# WL-FRONT.net
KiCad netlist of a schematic drawn in Altium Designer
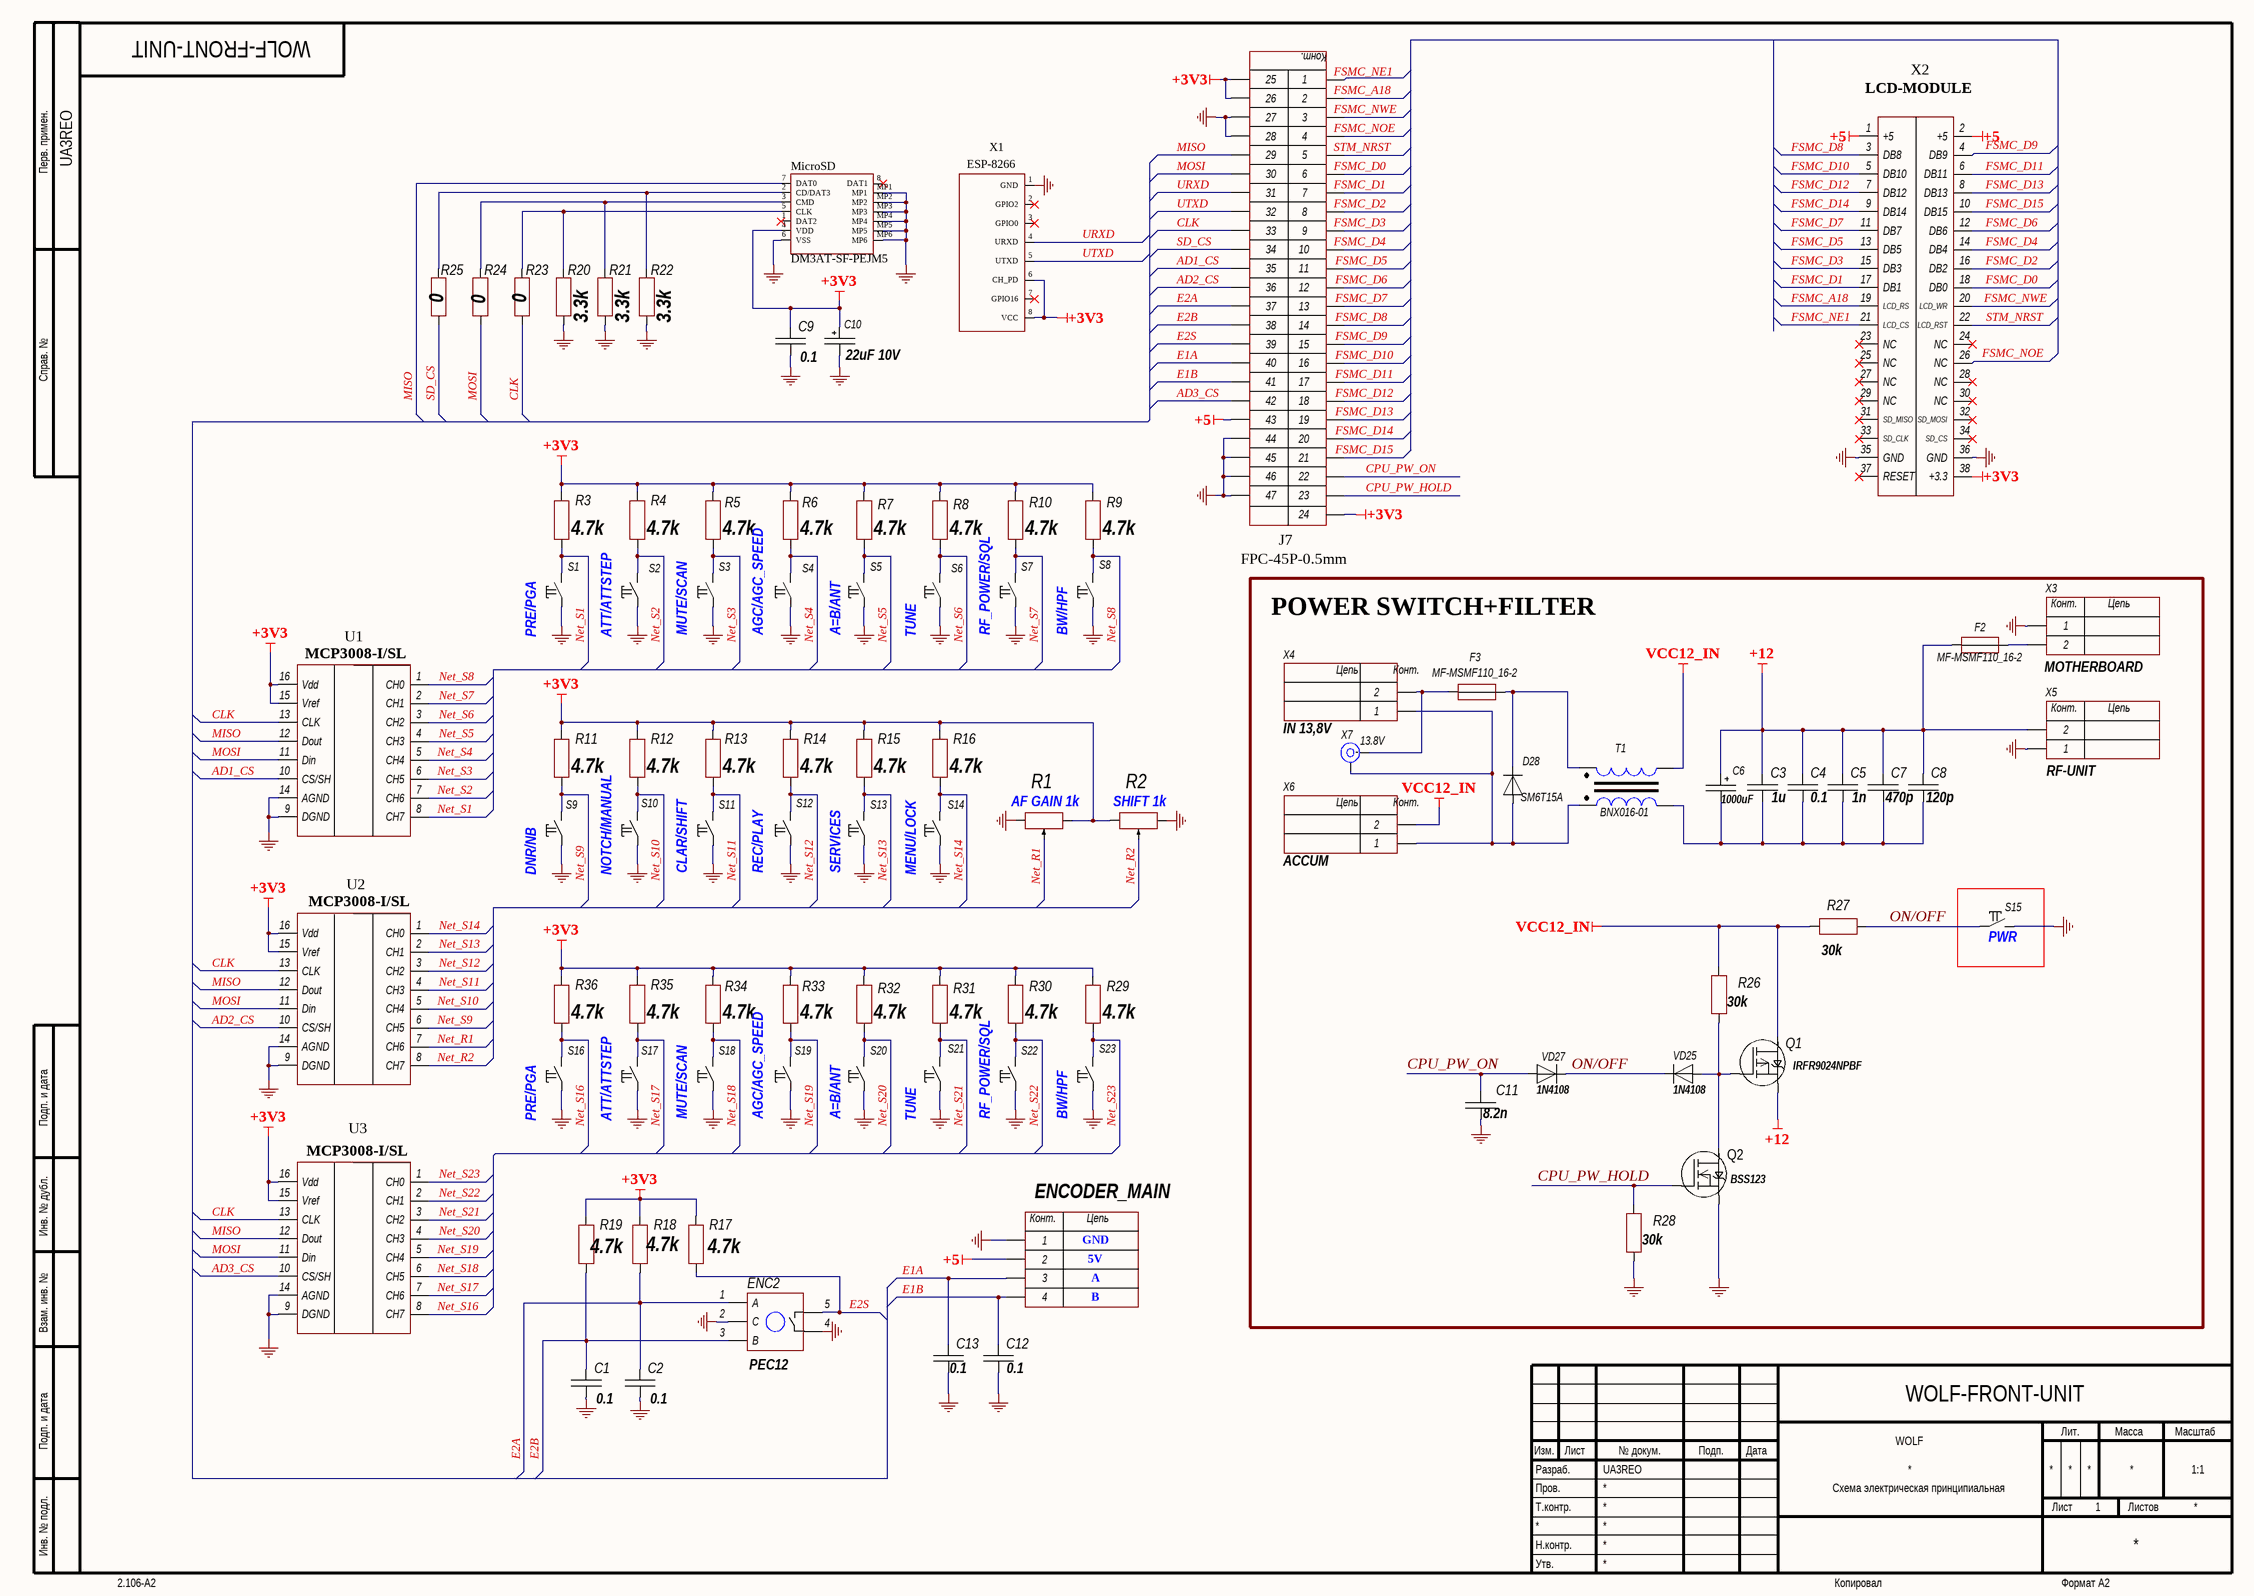
[diagram p0: WL-FRONT.SchDoc]

(export (version "E")
  (design (tool "Eeschema 10.0.6"))
  (components
    (comp (ref "C1")
      (value "0.1")
      (footprint "standard:CH0805C")
      (libsource (lib "Discrete") (part "Capacitor"))
    )
    (comp (ref "C2")
      (value "0.1")
      (footprint "standard:CH0805C")
      (libsource (lib "Discrete") (part "Capacitor"))
    )
    (comp (ref "C3")
      (value "1u")
      (footprint "standard:CH0805C")
      (libsource (lib "Discrete") (part "Capacitor"))
    )
    (comp (ref "C4")
      (value "0.1")
      (footprint "standard:CH0805C")
      (libsource (lib "Discrete") (part "Capacitor"))
    )
    (comp (ref "C5")
      (value "1n")
      (footprint "standard:CH0805C")
      (libsource (lib "Discrete") (part "Capacitor"))
    )
    (comp (ref "C6")
      (value "1000uF")
      (footprint "standard:D5C2H11")
      (libsource (lib "Discrete") (part "AlumCap"))
    )
    (comp (ref "C7")
      (value "470p")
      (footprint "standard:CH0805C")
      (libsource (lib "Discrete") (part "Capacitor"))
    )
    (comp (ref "C8")
      (value "120p")
      (footprint "standard:CH0805C")
      (libsource (lib "Discrete") (part "Capacitor"))
    )
    (comp (ref "C9")
      (value "0.1")
      (footprint "standard:CH0805C")
      (libsource (lib "Discrete") (part "Capacitor"))
    )
    (comp (ref "C10")
      (value "22uF 10V")
      (footprint "standard:TANTAL_B")
      (libsource (lib "Discrete") (part "TantalCap"))
    )
    (comp (ref "C11")
      (value "8.2n")
      (footprint "standard:CH0805C")
      (libsource (lib "Discrete") (part "Capacitor"))
    )
    (comp (ref "C12")
      (value "0.1")
      (footprint "standard:CH0805C")
      (libsource (lib "Discrete") (part "Capacitor"))
    )
    (comp (ref "C13") (value "0.1") (footprint "standard:CH0805C") (libsource (lib "") (part "Capacitor_1")))
    (comp (ref "D28") (value "SM6T15A") (footprint "standard:SOD123") (libsource (lib "Diods") (part "Diod")))
    (comp (ref "ENC2")
      (value "PEC12")
      (footprint "custom:ENC: PEC-12")
      (description "Encoder")
      (libsource (lib "Connectors") (part "PEC12"))
    )
    (comp (ref "ENCODER_MAIN")
      (value "*")
      (footprint "custom:CON: 0010321041")
      (libsource (lib "Connectors") (part "4-Connector"))
    )
    (comp (ref "F2")
      (value "MF-MSMF110_16-2")
      (footprint "standard:CH0603F")
      (libsource (lib "") (part "Fuse_1"))
    )
    (comp (ref "F3")
      (value "MF-MSMF110_16-2")
      (footprint "standard:CH0603F")
      (libsource (lib "Discrete") (part "Fuse"))
    )
    (comp (ref "J7")
      (value "FPC-45P-0.5mm")
      (footprint "FPC-45-0.5")
      (libsource (lib "Connectors") (part "47-PIN"))
    )
    (comp (ref "MicroSD") (value "DM3AT-SF-PEJM5") (libsource (lib "Discrete") (part "MicroSD")))
    (comp (ref "Q1")
      (value "IRFR9024NPBF")
      (footprint "D2PAK_132")
      (libsource (lib "Transistor") (part "P-KANAL"))
    )
    (comp (ref "Q2") (value "BSS123") (footprint "SOT23_132") (libsource (lib "Transistor") (part "N-KANAL")))
    (comp (ref "R1")
      (value "AF GAIN 1k")
      (footprint "custom:RES: 3296W")
      (libsource (lib "Discrete") (part "ADJ resistor"))
    )
    (comp (ref "R2")
      (value "SHIFT 1k")
      (footprint "custom:RES: 3296W")
      (libsource (lib "Discrete") (part "ADJ resistor"))
    )
    (comp (ref "R3")
      (value "4.7k")
      (footprint "standard:CH0805R")
      (libsource (lib "Discrete") (part "Resistor"))
    )
    (comp (ref "R4")
      (value "4.7k")
      (footprint "standard:CH0805R")
      (libsource (lib "Discrete") (part "Resistor"))
    )
    (comp (ref "R5")
      (value "4.7k")
      (footprint "standard:CH0805R")
      (libsource (lib "Discrete") (part "Resistor"))
    )
    (comp (ref "R6")
      (value "4.7k")
      (footprint "standard:CH0805R")
      (libsource (lib "Discrete") (part "Resistor"))
    )
    (comp (ref "R7")
      (value "4.7k")
      (footprint "standard:CH0805R")
      (libsource (lib "Discrete") (part "Resistor"))
    )
    (comp (ref "R8")
      (value "4.7k")
      (footprint "standard:CH0805R")
      (libsource (lib "Discrete") (part "Resistor"))
    )
    (comp (ref "R9")
      (value "4.7k")
      (footprint "standard:CH0805R")
      (libsource (lib "Discrete") (part "Resistor"))
    )
    (comp (ref "R10")
      (value "4.7k")
      (footprint "standard:CH0805R")
      (libsource (lib "Discrete") (part "Resistor"))
    )
    (comp (ref "R11")
      (value "4.7k")
      (footprint "standard:CH0805R")
      (libsource (lib "Discrete") (part "Resistor"))
    )
    (comp (ref "R12")
      (value "4.7k")
      (footprint "standard:CH0805R")
      (libsource (lib "Discrete") (part "Resistor"))
    )
    (comp (ref "R13")
      (value "4.7k")
      (footprint "standard:CH0805R")
      (libsource (lib "Discrete") (part "Resistor"))
    )
    (comp (ref "R14")
      (value "4.7k")
      (footprint "standard:CH0805R")
      (libsource (lib "Discrete") (part "Resistor"))
    )
    (comp (ref "R15")
      (value "4.7k")
      (footprint "standard:CH0805R")
      (libsource (lib "Discrete") (part "Resistor"))
    )
    (comp (ref "R16")
      (value "4.7k")
      (footprint "standard:CH0805R")
      (libsource (lib "Discrete") (part "Resistor"))
    )
    (comp (ref "R17")
      (value "4.7k")
      (footprint "standard:CH0805R")
      (libsource (lib "Discrete") (part "Resistor"))
    )
    (comp (ref "R18")
      (value "4.7k")
      (footprint "standard:CH0805R")
      (libsource (lib "Discrete") (part "Resistor"))
    )
    (comp (ref "R19")
      (value "4.7k")
      (footprint "standard:CH0805R")
      (libsource (lib "Discrete") (part "Resistor"))
    )
    (comp (ref "R20")
      (value "3.3k")
      (footprint "standard:CH0805R")
      (libsource (lib "Discrete") (part "Resistor"))
    )
    (comp (ref "R21")
      (value "3.3k")
      (footprint "standard:CH0805R")
      (libsource (lib "Discrete") (part "Resistor"))
    )
    (comp (ref "R22")
      (value "3.3k")
      (footprint "standard:CH0805R")
      (libsource (lib "Discrete") (part "Resistor"))
    )
    (comp (ref "R23") (value "0") (footprint "standard:CH0805R") (libsource (lib "") (part "Resistor_1")))
    (comp (ref "R24") (value "0") (footprint "standard:CH0805R") (libsource (lib "") (part "Resistor_1")))
    (comp (ref "R25") (value "0") (footprint "standard:CH0805R") (libsource (lib "") (part "Resistor_1")))
    (comp (ref "R26")
      (value "30k")
      (footprint "standard:CH0805R")
      (libsource (lib "Discrete") (part "Resistor"))
    )
    (comp (ref "R27") (value "30k") (footprint "standard:CH0805R") (libsource (lib "") (part "Resistor_2")))
    (comp (ref "R28")
      (value "30k")
      (footprint "standard:CH0805R")
      (libsource (lib "Discrete") (part "Resistor"))
    )
    (comp (ref "R29")
      (value "4.7k")
      (footprint "standard:CH0805R")
      (libsource (lib "Discrete") (part "Resistor"))
    )
    (comp (ref "R30")
      (value "4.7k")
      (footprint "standard:CH0805R")
      (libsource (lib "Discrete") (part "Resistor"))
    )
    (comp (ref "R31")
      (value "4.7k")
      (footprint "standard:CH0805R")
      (libsource (lib "Discrete") (part "Resistor"))
    )
    (comp (ref "R32")
      (value "4.7k")
      (footprint "standard:CH0805R")
      (libsource (lib "Discrete") (part "Resistor"))
    )
    (comp (ref "R33")
      (value "4.7k")
      (footprint "standard:CH0805R")
      (libsource (lib "Discrete") (part "Resistor"))
    )
    (comp (ref "R34")
      (value "4.7k")
      (footprint "standard:CH0805R")
      (libsource (lib "Discrete") (part "Resistor"))
    )
    (comp (ref "R35")
      (value "4.7k")
      (footprint "standard:CH0805R")
      (libsource (lib "Discrete") (part "Resistor"))
    )
    (comp (ref "R36")
      (value "4.7k")
      (footprint "standard:CH0805R")
      (libsource (lib "Discrete") (part "Resistor"))
    )
    (comp (ref "S1")
      (value "PRE/PGA")
      (footprint "Botoom-1")
      (description "6x6 mm")
      (libsource (lib "Connectors") (part "Tactile switches"))
    )
    (comp (ref "S2")
      (value "ATT/ATTSTEP")
      (footprint "Botoom-1")
      (description "6x6 mm")
      (libsource (lib "Connectors") (part "Tactile switches"))
    )
    (comp (ref "S3")
      (value "MUTE/SCAN")
      (footprint "Botoom-1")
      (description "6x6 mm")
      (libsource (lib "Connectors") (part "Tactile switches"))
    )
    (comp (ref "S4")
      (value "AGC/AGC_SPEED")
      (footprint "Botoom-1")
      (description "6x6 mm")
      (libsource (lib "Connectors") (part "Tactile switches"))
    )
    (comp (ref "S5")
      (value "A=B/ANT")
      (footprint "Botoom-1")
      (description "6x6 mm")
      (libsource (lib "Connectors") (part "Tactile switches"))
    )
    (comp (ref "S6")
      (value "TUNE")
      (footprint "Botoom-1")
      (description "6x6 mm")
      (libsource (lib "Connectors") (part "Tactile switches"))
    )
    (comp (ref "S7")
      (value "RF_POWER/SQL")
      (footprint "Botoom-1")
      (description "6x6 mm")
      (libsource (lib "Connectors") (part "Tactile switches"))
    )
    (comp (ref "S8")
      (value "BW/HPF")
      (footprint "Botoom-1")
      (description "6x6 mm")
      (libsource (lib "Connectors") (part "Tactile switches"))
    )
    (comp (ref "S9")
      (value "DNR/NB")
      (footprint "Botoom-1")
      (description "6x6 mm")
      (libsource (lib "Connectors") (part "Tactile switches"))
    )
    (comp (ref "S10")
      (value "NOTCH/MANUAL")
      (footprint "Botoom-1")
      (description "6x6 mm")
      (libsource (lib "Connectors") (part "Tactile switches"))
    )
    (comp (ref "S11")
      (value "CLAR/SHIFT")
      (footprint "Botoom-1")
      (description "6x6 mm")
      (libsource (lib "Connectors") (part "Tactile switches"))
    )
    (comp (ref "S12")
      (value "REC/PLAY")
      (footprint "Botoom-1")
      (description "6x6 mm")
      (libsource (lib "Connectors") (part "Tactile switches"))
    )
    (comp (ref "S13")
      (value "SERVICES")
      (footprint "Botoom-1")
      (description "6x6 mm")
      (libsource (lib "Connectors") (part "Tactile switches"))
    )
    (comp (ref "S14")
      (value "MENU/LOCK")
      (footprint "Botoom-1")
      (description "6x6 mm")
      (libsource (lib "Connectors") (part "Tactile switches"))
    )
    (comp (ref "S15")
      (value "PWR")
      (footprint "Botoom-1")
      (description "6x6 mm")
      (libsource (lib "Connectors") (part "Tactile switches"))
    )
    (comp (ref "S16")
      (value "PRE/PGA")
      (footprint "Botoom-1")
      (description "6x6 mm")
      (libsource (lib "Connectors") (part "Tactile switches"))
    )
    (comp (ref "S17")
      (value "ATT/ATTSTEP")
      (footprint "Botoom-1")
      (description "6x6 mm")
      (libsource (lib "Connectors") (part "Tactile switches"))
    )
    (comp (ref "S18")
      (value "MUTE/SCAN")
      (footprint "Botoom-1")
      (description "6x6 mm")
      (libsource (lib "Connectors") (part "Tactile switches"))
    )
    (comp (ref "S19")
      (value "AGC/AGC_SPEED")
      (footprint "Botoom-1")
      (description "6x6 mm")
      (libsource (lib "Connectors") (part "Tactile switches"))
    )
    (comp (ref "S20")
      (value "A=B/ANT")
      (footprint "Botoom-1")
      (description "6x6 mm")
      (libsource (lib "Connectors") (part "Tactile switches"))
    )
    (comp (ref "S21")
      (value "TUNE")
      (footprint "Botoom-1")
      (description "6x6 mm")
      (libsource (lib "Connectors") (part "Tactile switches"))
    )
    (comp (ref "S22")
      (value "RF_POWER/SQL")
      (footprint "Botoom-1")
      (description "6x6 mm")
      (libsource (lib "Connectors") (part "Tactile switches"))
    )
    (comp (ref "S23")
      (value "BW/HPF")
      (footprint "Botoom-1")
      (description "6x6 mm")
      (libsource (lib "Connectors") (part "Tactile switches"))
    )
    (comp (ref "T1")
      (value "BNX016-01")
      (footprint "custom:TRANS: DLW21")
      (fields (field (name "MANUFACTURER") "Murata Electronics North America"))
      (libsource (lib "Transformers") (part "EMI bead"))
    )
    (comp (ref "U1")
      (value "MCP3008-I/SL")
      (footprint "16-SOIC")
      (libsource (lib "Digital") (part "MCP3008-I/SL"))
    )
    (comp (ref "U2")
      (value "MCP3008-I/SL")
      (footprint "16-SOIC")
      (libsource (lib "Digital") (part "MCP3008-I/SL"))
    )
    (comp (ref "U3")
      (value "MCP3008-I/SL")
      (footprint "16-SOIC")
      (libsource (lib "Digital") (part "MCP3008-I/SL"))
    )
    (comp (ref "VD25") (value "1N4108") (footprint "1N4148") (libsource (lib "Diods") (part "Diod")))
    (comp (ref "VD27") (value "1N4108") (footprint "1N4148") (libsource (lib "Diods") (part "Diod")))
    (comp (ref "X1") (value "ESP-8266") (libsource (lib "Discrete") (part "ESP-8266")))
    (comp (ref "X2")
      (value "LCD-MODULE")
      (footprint "TFT3.2-320x480-pin")
      (libsource (lib "Digital") (part "LCD-MODULE"))
    )
    (comp (ref "X3")
      (value "MOTHERBOARD")
      (footprint "custom:CON: 300-02P-5.0")
      (libsource (lib "") (part "2-Connector_1"))
    )
    (comp (ref "X4")
      (value "IN 13,8V")
      (footprint "custom:CON: 300-02P-5.0")
      (libsource (lib "") (part "2-Connector_2"))
    )
    (comp (ref "X5")
      (value "RF-UNIT")
      (footprint "custom:CON: 300-02P-5.0")
      (libsource (lib "Connectors") (part "2-Connector"))
    )
    (comp (ref "X6")
      (value "ACCUM")
      (footprint "custom:CON: 300-02P-5.0")
      (libsource (lib "") (part "2-Connector_2"))
    )
    (comp (ref "X7")
      (value "13.8V")
      (footprint "custom:CON: PJ-102AH")
      (description "RF")
      (fields (field (name "MANUFACTURER") "CUI Inc."))
      (libsource (lib "Connectors") (part "Power"))
    )
  )
  (nets
    (net (code "1") (name "+3V3") (class "Default")
      (node (ref "C10") (pin "1") (pinfunction "1_1") (pintype "power_in"))
      (node (ref "C9") (pin "2") (pinfunction "2_2") (pintype "power_in"))
      (node (ref "J7") (pin "24") (pinfunction "24_24") (pintype "power_in"))
      (node (ref "J7") (pin "25") (pinfunction "25_25") (pintype "power_in"))
      (node (ref "J7") (pin "26") (pinfunction "26_26") (pintype "power_in"))
      (node (ref "MicroSD") (pin "4") (pinfunction "VDD_4") (pintype "passive"))
      (node (ref "R1") (pin "3") (pinfunction "3_3") (pintype "passive"))
      (node (ref "R10") (pin "2") (pinfunction "2_2") (pintype "passive"))
      (node (ref "R11") (pin "2") (pinfunction "2_2") (pintype "passive"))
      (node (ref "R12") (pin "2") (pinfunction "2_2") (pintype "passive"))
      (node (ref "R13") (pin "2") (pinfunction "2_2") (pintype "passive"))
      (node (ref "R14") (pin "2") (pinfunction "2_2") (pintype "passive"))
      (node (ref "R15") (pin "2") (pinfunction "2_2") (pintype "passive"))
      (node (ref "R16") (pin "2") (pinfunction "2_2") (pintype "passive"))
      (node (ref "R17") (pin "2") (pinfunction "2_2") (pintype "passive"))
      (node (ref "R18") (pin "2") (pinfunction "2_2") (pintype "passive"))
      (node (ref "R19") (pin "2") (pinfunction "2_2") (pintype "passive"))
      (node (ref "R2") (pin "1") (pinfunction "1_1") (pintype "passive"))
      (node (ref "R29") (pin "2") (pinfunction "2_2") (pintype "passive"))
      (node (ref "R3") (pin "2") (pinfunction "2_2") (pintype "passive"))
      (node (ref "R30") (pin "2") (pinfunction "2_2") (pintype "passive"))
      (node (ref "R31") (pin "2") (pinfunction "2_2") (pintype "passive"))
      (node (ref "R32") (pin "2") (pinfunction "2_2") (pintype "passive"))
      (node (ref "R33") (pin "2") (pinfunction "2_2") (pintype "passive"))
      (node (ref "R34") (pin "2") (pinfunction "2_2") (pintype "passive"))
      (node (ref "R35") (pin "2") (pinfunction "2_2") (pintype "passive"))
      (node (ref "R36") (pin "2") (pinfunction "2_2") (pintype "passive"))
      (node (ref "R4") (pin "2") (pinfunction "2_2") (pintype "passive"))
      (node (ref "R5") (pin "2") (pinfunction "2_2") (pintype "passive"))
      (node (ref "R6") (pin "2") (pinfunction "2_2") (pintype "passive"))
      (node (ref "R7") (pin "2") (pinfunction "2_2") (pintype "passive"))
      (node (ref "R8") (pin "2") (pinfunction "2_2") (pintype "passive"))
      (node (ref "R9") (pin "2") (pinfunction "2_2") (pintype "passive"))
      (node (ref "U1") (pin "15") (pinfunction "Vref_15") (pintype "passive"))
      (node (ref "U1") (pin "16") (pinfunction "Vdd_16") (pintype "passive"))
      (node (ref "U2") (pin "15") (pinfunction "Vref_15") (pintype "passive"))
      (node (ref "U2") (pin "16") (pinfunction "Vdd_16") (pintype "passive"))
      (node (ref "U3") (pin "15") (pinfunction "Vref_15") (pintype "passive"))
      (node (ref "U3") (pin "16") (pinfunction "Vdd_16") (pintype "passive"))
      (node (ref "X1") (pin "6") (pinfunction "CH_PD_6") (pintype "passive"))
      (node (ref "X1") (pin "8") (pinfunction "VCC_8") (pintype "passive"))
      (node (ref "X2") (pin "38") (pinfunction "+3.3_38") (pintype "passive"))
    )
    (net (code "2") (name "+5") (class "Default")
      (node (ref "ENCODER_MAIN") (pin "2") (pinfunction "2_2") (pintype "passive"))
      (node (ref "J7") (pin "43") (pinfunction "43_43") (pintype "power_in"))
      (node (ref "X2") (pin "1") (pinfunction "+5_1") (pintype "passive"))
      (node (ref "X2") (pin "2") (pinfunction "+5_2") (pintype "passive"))
    )
    (net (code "3") (name "+12") (class "Default")
      (node (ref "C3") (pin "2") (pinfunction "2_2") (pintype "power_in"))
      (node (ref "C4") (pin "2") (pinfunction "2_2") (pintype "power_in"))
      (node (ref "C5") (pin "2") (pinfunction "2_2") (pintype "power_in"))
      (node (ref "C6") (pin "1") (pinfunction "1_1") (pintype "power_in"))
      (node (ref "C7") (pin "2") (pinfunction "2_2") (pintype "power_in"))
      (node (ref "C8") (pin "2") (pinfunction "2_2") (pintype "power_in"))
      (node (ref "F2") (pin "1") (pinfunction "1_1") (pintype "passive"))
      (node (ref "Q1") (pin "2") (pinfunction "I_2") (pintype "passive"))
      (node (ref "X5") (pin "2") (pinfunction "2_2") (pintype "passive"))
    )
    (net (code "4") (name "/AD1_CS") (class "Default")
      (node (ref "J7") (pin "35") (pinfunction "35_35") (pintype "power_in"))
      (node (ref "U1") (pin "10") (pinfunction "CS/SH_10") (pintype "passive"))
    )
    (net (code "5") (name "/AD2_CS") (class "Default")
      (node (ref "J7") (pin "36") (pinfunction "36_36") (pintype "power_in"))
      (node (ref "U2") (pin "10") (pinfunction "CS/SH_10") (pintype "passive"))
    )
    (net (code "6") (name "/AD3_CS") (class "Default")
      (node (ref "J7") (pin "42") (pinfunction "42_42") (pintype "power_in"))
      (node (ref "U3") (pin "10") (pinfunction "CS/SH_10") (pintype "passive"))
    )
    (net (code "7") (name "/CLK") (class "Default")
      (node (ref "J7") (pin "33") (pinfunction "33_33") (pintype "power_in"))
      (node (ref "R23") (pin "2") (pinfunction "2_2") (pintype "passive"))
      (node (ref "U1") (pin "13") (pinfunction "CLK_13") (pintype "passive"))
      (node (ref "U2") (pin "13") (pinfunction "CLK_13") (pintype "passive"))
      (node (ref "U3") (pin "13") (pinfunction "CLK_13") (pintype "passive"))
    )
    (net (code "8") (name "/CPU_PW_HOLD") (class "Default")
      (node (ref "J7") (pin "23") (pinfunction "23_23") (pintype "power_in"))
      (node (ref "Q2") (pin "1") (pinfunction "Затвор(Gate)_1") (pintype "passive"))
      (node (ref "R28") (pin "2") (pinfunction "2_2") (pintype "passive"))
    )
    (net (code "9") (name "/CPU_PW_ON") (class "Default")
      (node (ref "C11") (pin "1") (pinfunction "1_1") (pintype "power_in"))
      (node (ref "J7") (pin "22") (pinfunction "22_22") (pintype "power_in"))
      (node (ref "VD27") (pin "1") (pinfunction "1_1") (pintype "passive"))
    )
    (net (code "10") (name "/E1A") (class "Default")
      (node (ref "C13") (pin "2") (pinfunction "2_2") (pintype "power_in"))
      (node (ref "ENCODER_MAIN") (pin "3") (pinfunction "3_3") (pintype "power_in"))
      (node (ref "J7") (pin "40") (pinfunction "40_40") (pintype "power_in"))
    )
    (net (code "11") (name "/E1B") (class "Default")
      (node (ref "C12") (pin "2") (pinfunction "2_2") (pintype "power_in"))
      (node (ref "ENCODER_MAIN") (pin "4") (pinfunction "4_4") (pintype "power_in"))
      (node (ref "J7") (pin "41") (pinfunction "41_41") (pintype "power_in"))
    )
    (net (code "12") (name "/E2A") (class "Default")
      (node (ref "C2") (pin "2") (pinfunction "2_2") (pintype "power_in"))
      (node (ref "ENC2") (pin "1") (pinfunction "A_1") (pintype "passive"))
      (node (ref "J7") (pin "37") (pinfunction "37_37") (pintype "power_in"))
      (node (ref "R18") (pin "1") (pinfunction "1_1") (pintype "passive"))
    )
    (net (code "13") (name "/E2B") (class "Default")
      (node (ref "C1") (pin "2") (pinfunction "2_2") (pintype "power_in"))
      (node (ref "ENC2") (pin "3") (pinfunction "B_3") (pintype "passive"))
      (node (ref "J7") (pin "38") (pinfunction "38_38") (pintype "power_in"))
      (node (ref "R19") (pin "1") (pinfunction "1_1") (pintype "passive"))
    )
    (net (code "14") (name "/E2S") (class "Default")
      (node (ref "ENC2") (pin "5") (pinfunction "5_5") (pintype "passive"))
      (node (ref "J7") (pin "39") (pinfunction "39_39") (pintype "power_in"))
      (node (ref "R17") (pin "1") (pinfunction "1_1") (pintype "passive"))
    )
    (net (code "15") (name "/FSMC_A18") (class "Default")
      (node (ref "X2") (pin "19") (pinfunction "LCD_RS_19") (pintype "passive"))
    )
    (net (code "16") (name "/FSMC_D0") (class "Default")
      (node (ref "X2") (pin "18") (pinfunction "DB0_18") (pintype "passive"))
    )
    (net (code "17") (name "/FSMC_D1") (class "Default")
      (node (ref "X2") (pin "17") (pinfunction "DB1_17") (pintype "passive"))
    )
    (net (code "18") (name "/FSMC_D2") (class "Default")
      (node (ref "X2") (pin "16") (pinfunction "DB2_16") (pintype "passive"))
    )
    (net (code "19") (name "/FSMC_D3") (class "Default")
      (node (ref "X2") (pin "15") (pinfunction "DB3_15") (pintype "passive"))
    )
    (net (code "20") (name "/FSMC_D4") (class "Default")
      (node (ref "X2") (pin "14") (pinfunction "DB4_14") (pintype "passive"))
    )
    (net (code "21") (name "/FSMC_D5") (class "Default")
      (node (ref "X2") (pin "13") (pinfunction "DB5_13") (pintype "passive"))
    )
    (net (code "22") (name "/FSMC_D6") (class "Default")
      (node (ref "X2") (pin "12") (pinfunction "DB6_12") (pintype "passive"))
    )
    (net (code "23") (name "/FSMC_D7") (class "Default")
      (node (ref "X2") (pin "11") (pinfunction "DB7_11") (pintype "passive"))
    )
    (net (code "24") (name "/FSMC_D8") (class "Default")
      (node (ref "X2") (pin "3") (pinfunction "DB8_3") (pintype "passive"))
    )
    (net (code "25") (name "/FSMC_D9") (class "Default")
      (node (ref "X2") (pin "4") (pinfunction "DB9_4") (pintype "passive"))
    )
    (net (code "26") (name "/FSMC_D10") (class "Default")
      (node (ref "X2") (pin "5") (pinfunction "DB10_5") (pintype "passive"))
    )
    (net (code "27") (name "/FSMC_D11") (class "Default")
      (node (ref "X2") (pin "6") (pinfunction "DB11_6") (pintype "passive"))
    )
    (net (code "28") (name "/FSMC_D12") (class "Default")
      (node (ref "X2") (pin "7") (pinfunction "DB12_7") (pintype "passive"))
    )
    (net (code "29") (name "/FSMC_D13") (class "Default")
      (node (ref "X2") (pin "8") (pinfunction "DB13_8") (pintype "passive"))
    )
    (net (code "30") (name "/FSMC_D14") (class "Default")
      (node (ref "X2") (pin "9") (pinfunction "DB14_9") (pintype "passive"))
    )
    (net (code "31") (name "/FSMC_D15") (class "Default")
      (node (ref "X2") (pin "10") (pinfunction "DB15_10") (pintype "passive"))
    )
    (net (code "32") (name "/FSMC_NE1") (class "Default")
      (node (ref "X2") (pin "21") (pinfunction "LCD_CS_21") (pintype "passive"))
    )
    (net (code "33") (name "/FSMC_NOE") (class "Default")
      (node (ref "X2") (pin "26") (pinfunction "NC_26") (pintype "passive"))
    )
    (net (code "34") (name "/FSMC_NWE") (class "Default")
      (node (ref "X2") (pin "20") (pinfunction "LCD_WR_20") (pintype "passive"))
    )
    (net (code "35") (name "/MISO") (class "Default")
      (node (ref "J7") (pin "29") (pinfunction "29_29") (pintype "power_in"))
      (node (ref "MicroSD") (pin "7") (pinfunction "DAT0_7") (pintype "passive"))
      (node (ref "U1") (pin "12") (pinfunction "Dout_12") (pintype "passive"))
      (node (ref "U2") (pin "12") (pinfunction "Dout_12") (pintype "passive"))
      (node (ref "U3") (pin "12") (pinfunction "Dout_12") (pintype "passive"))
    )
    (net (code "36") (name "/MOSI") (class "Default")
      (node (ref "J7") (pin "30") (pinfunction "30_30") (pintype "power_in"))
      (node (ref "R24") (pin "2") (pinfunction "2_2") (pintype "passive"))
      (node (ref "U1") (pin "11") (pinfunction "Din_11") (pintype "passive"))
      (node (ref "U2") (pin "11") (pinfunction "Din_11") (pintype "passive"))
      (node (ref "U3") (pin "11") (pinfunction "Din_11") (pintype "passive"))
    )
    (net (code "37") (name "/Net_R1") (class "Default")
      (node (ref "R1") (pin "2") (pinfunction "2_2") (pintype "passive"))
      (node (ref "U2") (pin "7") (pinfunction "CH6_7") (pintype "passive"))
    )
    (net (code "38") (name "/Net_R2") (class "Default")
      (node (ref "R2") (pin "2") (pinfunction "2_2") (pintype "passive"))
      (node (ref "U2") (pin "8") (pinfunction "CH7_8") (pintype "passive"))
    )
    (net (code "39") (name "/Net_S1") (class "Default")
      (node (ref "R3") (pin "1") (pinfunction "1_1") (pintype "passive"))
      (node (ref "S1") (pin "2") (pinfunction "2_2") (pintype "passive"))
      (node (ref "U1") (pin "8") (pinfunction "CH7_8") (pintype "passive"))
    )
    (net (code "40") (name "/Net_S2") (class "Default")
      (node (ref "R4") (pin "1") (pinfunction "1_1") (pintype "passive"))
      (node (ref "S2") (pin "2") (pinfunction "2_2") (pintype "passive"))
      (node (ref "U1") (pin "7") (pinfunction "CH6_7") (pintype "passive"))
    )
    (net (code "41") (name "/Net_S3") (class "Default")
      (node (ref "R5") (pin "1") (pinfunction "1_1") (pintype "passive"))
      (node (ref "S3") (pin "2") (pinfunction "2_2") (pintype "passive"))
      (node (ref "U1") (pin "6") (pinfunction "CH5_6") (pintype "passive"))
    )
    (net (code "42") (name "/Net_S4") (class "Default")
      (node (ref "R6") (pin "1") (pinfunction "1_1") (pintype "passive"))
      (node (ref "S4") (pin "2") (pinfunction "2_2") (pintype "passive"))
      (node (ref "U1") (pin "5") (pinfunction "CH4_5") (pintype "passive"))
    )
    (net (code "43") (name "/Net_S5") (class "Default")
      (node (ref "R7") (pin "1") (pinfunction "1_1") (pintype "passive"))
      (node (ref "S5") (pin "2") (pinfunction "2_2") (pintype "passive"))
      (node (ref "U1") (pin "4") (pinfunction "CH3_4") (pintype "passive"))
    )
    (net (code "44") (name "/Net_S6") (class "Default")
      (node (ref "R8") (pin "1") (pinfunction "1_1") (pintype "passive"))
      (node (ref "S6") (pin "2") (pinfunction "2_2") (pintype "passive"))
      (node (ref "U1") (pin "3") (pinfunction "CH2_3") (pintype "passive"))
    )
    (net (code "45") (name "/Net_S7") (class "Default")
      (node (ref "R10") (pin "1") (pinfunction "1_1") (pintype "passive"))
      (node (ref "S7") (pin "2") (pinfunction "2_2") (pintype "passive"))
      (node (ref "U1") (pin "2") (pinfunction "CH1_2") (pintype "passive"))
    )
    (net (code "46") (name "/Net_S8") (class "Default")
      (node (ref "R9") (pin "1") (pinfunction "1_1") (pintype "passive"))
      (node (ref "S8") (pin "2") (pinfunction "2_2") (pintype "passive"))
      (node (ref "U1") (pin "1") (pinfunction "CH0_1") (pintype "passive"))
    )
    (net (code "47") (name "/Net_S9") (class "Default")
      (node (ref "R11") (pin "1") (pinfunction "1_1") (pintype "passive"))
      (node (ref "S9") (pin "2") (pinfunction "2_2") (pintype "passive"))
      (node (ref "U2") (pin "6") (pinfunction "CH5_6") (pintype "passive"))
    )
    (net (code "48") (name "/Net_S10") (class "Default")
      (node (ref "R12") (pin "1") (pinfunction "1_1") (pintype "passive"))
      (node (ref "S10") (pin "2") (pinfunction "2_2") (pintype "passive"))
      (node (ref "U2") (pin "5") (pinfunction "CH4_5") (pintype "passive"))
    )
    (net (code "49") (name "/Net_S11") (class "Default")
      (node (ref "R13") (pin "1") (pinfunction "1_1") (pintype "passive"))
      (node (ref "S11") (pin "2") (pinfunction "2_2") (pintype "passive"))
      (node (ref "U2") (pin "4") (pinfunction "CH3_4") (pintype "passive"))
    )
    (net (code "50") (name "/Net_S12") (class "Default")
      (node (ref "R14") (pin "1") (pinfunction "1_1") (pintype "passive"))
      (node (ref "S12") (pin "2") (pinfunction "2_2") (pintype "passive"))
      (node (ref "U2") (pin "3") (pinfunction "CH2_3") (pintype "passive"))
    )
    (net (code "51") (name "/Net_S13") (class "Default")
      (node (ref "R15") (pin "1") (pinfunction "1_1") (pintype "passive"))
      (node (ref "S13") (pin "2") (pinfunction "2_2") (pintype "passive"))
      (node (ref "U2") (pin "2") (pinfunction "CH1_2") (pintype "passive"))
    )
    (net (code "52") (name "/Net_S14") (class "Default")
      (node (ref "R16") (pin "1") (pinfunction "1_1") (pintype "passive"))
      (node (ref "S14") (pin "2") (pinfunction "2_2") (pintype "passive"))
      (node (ref "U2") (pin "1") (pinfunction "CH0_1") (pintype "passive"))
    )
    (net (code "53") (name "/Net_S16") (class "Default")
      (node (ref "R36") (pin "1") (pinfunction "1_1") (pintype "passive"))
      (node (ref "S16") (pin "2") (pinfunction "2_2") (pintype "passive"))
      (node (ref "U3") (pin "8") (pinfunction "CH7_8") (pintype "passive"))
    )
    (net (code "54") (name "/Net_S17") (class "Default")
      (node (ref "R35") (pin "1") (pinfunction "1_1") (pintype "passive"))
      (node (ref "S17") (pin "2") (pinfunction "2_2") (pintype "passive"))
      (node (ref "U3") (pin "7") (pinfunction "CH6_7") (pintype "passive"))
    )
    (net (code "55") (name "/Net_S18") (class "Default")
      (node (ref "R34") (pin "1") (pinfunction "1_1") (pintype "passive"))
      (node (ref "S18") (pin "2") (pinfunction "2_2") (pintype "passive"))
      (node (ref "U3") (pin "6") (pinfunction "CH5_6") (pintype "passive"))
    )
    (net (code "56") (name "/Net_S19") (class "Default")
      (node (ref "R33") (pin "1") (pinfunction "1_1") (pintype "passive"))
      (node (ref "S19") (pin "2") (pinfunction "2_2") (pintype "passive"))
      (node (ref "U3") (pin "5") (pinfunction "CH4_5") (pintype "passive"))
    )
    (net (code "57") (name "/Net_S20") (class "Default")
      (node (ref "R32") (pin "1") (pinfunction "1_1") (pintype "passive"))
      (node (ref "S20") (pin "2") (pinfunction "2_2") (pintype "passive"))
      (node (ref "U3") (pin "4") (pinfunction "CH3_4") (pintype "passive"))
    )
    (net (code "58") (name "/Net_S21") (class "Default")
      (node (ref "R31") (pin "1") (pinfunction "1_1") (pintype "passive"))
      (node (ref "S21") (pin "2") (pinfunction "2_2") (pintype "passive"))
      (node (ref "U3") (pin "3") (pinfunction "CH2_3") (pintype "passive"))
    )
    (net (code "59") (name "/Net_S22") (class "Default")
      (node (ref "R30") (pin "1") (pinfunction "1_1") (pintype "passive"))
      (node (ref "S22") (pin "2") (pinfunction "2_2") (pintype "passive"))
      (node (ref "U3") (pin "2") (pinfunction "CH1_2") (pintype "passive"))
    )
    (net (code "60") (name "/Net_S23") (class "Default")
      (node (ref "R29") (pin "1") (pinfunction "1_1") (pintype "passive"))
      (node (ref "S23") (pin "2") (pinfunction "2_2") (pintype "passive"))
      (node (ref "U3") (pin "1") (pinfunction "CH0_1") (pintype "passive"))
    )
    (net (code "61") (name "/ON{slash}OFF") (class "Default")
      (node (ref "R27") (pin "1") (pinfunction "1_1") (pintype "passive"))
      (node (ref "S15") (pin "1") (pinfunction "1_1") (pintype "passive"))
      (node (ref "VD25") (pin "2") (pinfunction "2_2") (pintype "passive"))
      (node (ref "VD27") (pin "2") (pinfunction "2_2") (pintype "passive"))
    )
    (net (code "62") (name "/SD_CS") (class "Default")
      (node (ref "J7") (pin "34") (pinfunction "34_34") (pintype "power_in"))
      (node (ref "R25") (pin "2") (pinfunction "2_2") (pintype "passive"))
    )
    (net (code "63") (name "/STM_NRST") (class "Default")
      (node (ref "X2") (pin "22") (pinfunction "LCD_RST_22") (pintype "passive"))
    )
    (net (code "64") (name "/URXD") (class "Default")
      (node (ref "J7") (pin "31") (pinfunction "31_31") (pintype "power_in"))
      (node (ref "X1") (pin "4") (pinfunction "URXD_4") (pintype "passive"))
    )
    (net (code "65") (name "/UTXD") (class "Default")
      (node (ref "J7") (pin "32") (pinfunction "32_32") (pintype "power_in"))
      (node (ref "X1") (pin "5") (pinfunction "UTXD_5") (pintype "passive"))
    )
    (net (code "66") (name "GND") (class "Default")
      (node (ref "C1") (pin "1") (pinfunction "1_1") (pintype "power_in"))
      (node (ref "C10") (pin "2") (pinfunction "2_2") (pintype "power_in"))
      (node (ref "C11") (pin "2") (pinfunction "2_2") (pintype "power_in"))
      (node (ref "C12") (pin "1") (pinfunction "1_1") (pintype "power_in"))
      (node (ref "C13") (pin "1") (pinfunction "1_1") (pintype "power_in"))
      (node (ref "C2") (pin "1") (pinfunction "1_1") (pintype "power_in"))
      (node (ref "C9") (pin "1") (pinfunction "1_1") (pintype "power_in"))
      (node (ref "ENC2") (pin "2") (pinfunction "C_2") (pintype "passive"))
      (node (ref "ENC2") (pin "4") (pinfunction "4_4") (pintype "passive"))
      (node (ref "ENCODER_MAIN") (pin "1") (pinfunction "1_1") (pintype "passive"))
      (node (ref "J7") (pin "27") (pinfunction "27_27") (pintype "power_in"))
      (node (ref "J7") (pin "28") (pinfunction "28_28") (pintype "power_in"))
      (node (ref "J7") (pin "44") (pinfunction "44_44") (pintype "power_in"))
      (node (ref "J7") (pin "45") (pinfunction "45_45") (pintype "power_in"))
      (node (ref "J7") (pin "46") (pinfunction "46_46") (pintype "power_in"))
      (node (ref "J7") (pin "47") (pinfunction "47_47") (pintype "power_in"))
      (node (ref "MicroSD") (pin "6") (pinfunction "VSS_6") (pintype "passive"))
      (node (ref "MicroSD") (pin "MP1") (pinfunction "MP1_MP1") (pintype "passive"))
      (node (ref "MicroSD") (pin "MP2") (pinfunction "MP2_MP2") (pintype "passive"))
      (node (ref "MicroSD") (pin "MP3") (pinfunction "MP3_MP3") (pintype "passive"))
      (node (ref "MicroSD") (pin "MP4") (pinfunction "MP4_MP4") (pintype "passive"))
      (node (ref "MicroSD") (pin "MP5") (pinfunction "MP5_MP5") (pintype "passive"))
      (node (ref "MicroSD") (pin "MP6") (pinfunction "MP6_MP6") (pintype "passive"))
      (node (ref "Q2") (pin "2") (pinfunction "I_2") (pintype "passive"))
      (node (ref "R1") (pin "1") (pinfunction "1_1") (pintype "passive"))
      (node (ref "R2") (pin "3") (pinfunction "3_3") (pintype "passive"))
      (node (ref "R20") (pin "1") (pinfunction "1_1") (pintype "passive"))
      (node (ref "R21") (pin "1") (pinfunction "1_1") (pintype "passive"))
      (node (ref "R22") (pin "1") (pinfunction "1_1") (pintype "passive"))
      (node (ref "R28") (pin "1") (pinfunction "1_1") (pintype "passive"))
      (node (ref "S1") (pin "1") (pinfunction "1_1") (pintype "passive"))
      (node (ref "S10") (pin "1") (pinfunction "1_1") (pintype "passive"))
      (node (ref "S11") (pin "1") (pinfunction "1_1") (pintype "passive"))
      (node (ref "S12") (pin "1") (pinfunction "1_1") (pintype "passive"))
      (node (ref "S13") (pin "1") (pinfunction "1_1") (pintype "passive"))
      (node (ref "S14") (pin "1") (pinfunction "1_1") (pintype "passive"))
      (node (ref "S15") (pin "2") (pinfunction "2_2") (pintype "passive"))
      (node (ref "S16") (pin "1") (pinfunction "1_1") (pintype "passive"))
      (node (ref "S17") (pin "1") (pinfunction "1_1") (pintype "passive"))
      (node (ref "S18") (pin "1") (pinfunction "1_1") (pintype "passive"))
      (node (ref "S19") (pin "1") (pinfunction "1_1") (pintype "passive"))
      (node (ref "S2") (pin "1") (pinfunction "1_1") (pintype "passive"))
      (node (ref "S20") (pin "1") (pinfunction "1_1") (pintype "passive"))
      (node (ref "S21") (pin "1") (pinfunction "1_1") (pintype "passive"))
      (node (ref "S22") (pin "1") (pinfunction "1_1") (pintype "passive"))
      (node (ref "S23") (pin "1") (pinfunction "1_1") (pintype "passive"))
      (node (ref "S3") (pin "1") (pinfunction "1_1") (pintype "passive"))
      (node (ref "S4") (pin "1") (pinfunction "1_1") (pintype "passive"))
      (node (ref "S5") (pin "1") (pinfunction "1_1") (pintype "passive"))
      (node (ref "S6") (pin "1") (pinfunction "1_1") (pintype "passive"))
      (node (ref "S7") (pin "1") (pinfunction "1_1") (pintype "passive"))
      (node (ref "S8") (pin "1") (pinfunction "1_1") (pintype "passive"))
      (node (ref "S9") (pin "1") (pinfunction "1_1") (pintype "passive"))
      (node (ref "U1") (pin "14") (pinfunction "AGND_14") (pintype "passive"))
      (node (ref "U1") (pin "9") (pinfunction "DGND_9") (pintype "passive"))
      (node (ref "U2") (pin "14") (pinfunction "AGND_14") (pintype "passive"))
      (node (ref "U2") (pin "9") (pinfunction "DGND_9") (pintype "passive"))
      (node (ref "U3") (pin "14") (pinfunction "AGND_14") (pintype "passive"))
      (node (ref "U3") (pin "9") (pinfunction "DGND_9") (pintype "passive"))
      (node (ref "X1") (pin "1") (pinfunction "GND_1") (pintype "passive"))
      (node (ref "X2") (pin "35") (pinfunction "GND_35") (pintype "passive"))
      (node (ref "X2") (pin "36") (pinfunction "GND_36") (pintype "passive"))
      (node (ref "X3") (pin "1") (pinfunction "1_1") (pintype "passive"))
      (node (ref "X5") (pin "1") (pinfunction "1_1") (pintype "passive"))
    )
    (net (code "67") (name "Net-(C3-Pad1)") (class "Default")
      (node (ref "C3") (pin "1") (pinfunction "1_1") (pintype "power_in"))
      (node (ref "C4") (pin "1") (pinfunction "1_1") (pintype "power_in"))
      (node (ref "C5") (pin "1") (pinfunction "1_1") (pintype "power_in"))
      (node (ref "C6") (pin "2") (pinfunction "2_2") (pintype "power_in"))
      (node (ref "C7") (pin "1") (pinfunction "1_1") (pintype "power_in"))
      (node (ref "C8") (pin "1") (pinfunction "1_1") (pintype "power_in"))
      (node (ref "T1") (pin "4") (pinfunction "4_4") (pintype "passive"))
    )
    (net (code "68") (name "Net-(D28-Pad1)") (class "Default")
      (node (ref "D28") (pin "1") (pinfunction "1_1") (pintype "passive"))
      (node (ref "T1") (pin "3") (pinfunction "3_3") (pintype "passive"))
      (node (ref "X4") (pin "1") (pinfunction "1_1") (pintype "passive"))
      (node (ref "X6") (pin "1") (pinfunction "1_1") (pintype "passive"))
      (node (ref "X7") (pin "2") (pinfunction "IN_2") (pintype "passive"))
    )
    (net (code "69") (name "Net-(D28-Pad2)") (class "Default")
      (node (ref "D28") (pin "2") (pinfunction "2_2") (pintype "passive"))
      (node (ref "F3") (pin "2") (pinfunction "2_2") (pintype "passive"))
      (node (ref "T1") (pin "1") (pinfunction "1_1") (pintype "passive"))
    )
    (net (code "70") (name "Net-(F2-Pad2)") (class "Default")
      (node (ref "F2") (pin "2") (pinfunction "2_2") (pintype "passive"))
      (node (ref "X3") (pin "2") (pinfunction "2_2") (pintype "passive"))
    )
    (net (code "71") (name "Net-(F3-Pad1)") (class "Default")
      (node (ref "F3") (pin "1") (pinfunction "1_1") (pintype "passive"))
      (node (ref "X4") (pin "2") (pinfunction "2_2") (pintype "passive"))
      (node (ref "X7") (pin "1") (pinfunction "IN_1") (pintype "passive"))
    )
    (net (code "72") (name "Net-(MicroSD-CD{slash}DAT3)") (class "Default")
      (node (ref "MicroSD") (pin "2") (pinfunction "CD/DAT3_2") (pintype "passive"))
      (node (ref "R22") (pin "2") (pinfunction "2_2") (pintype "passive"))
      (node (ref "R25") (pin "1") (pinfunction "1_1") (pintype "passive"))
    )
    (net (code "73") (name "Net-(MicroSD-CLK)") (class "Default")
      (node (ref "MicroSD") (pin "5") (pinfunction "CLK_5") (pintype "passive"))
      (node (ref "R20") (pin "2") (pinfunction "2_2") (pintype "passive"))
      (node (ref "R23") (pin "1") (pinfunction "1_1") (pintype "passive"))
    )
    (net (code "74") (name "Net-(MicroSD-CMD)") (class "Default")
      (node (ref "MicroSD") (pin "3") (pinfunction "CMD_3") (pintype "passive"))
      (node (ref "R21") (pin "2") (pinfunction "2_2") (pintype "passive"))
      (node (ref "R24") (pin "1") (pinfunction "1_1") (pintype "passive"))
    )
    (net (code "75") (name "Net-(Q1-Затвор(Gate))") (class "Default")
      (node (ref "Q1") (pin "1") (pinfunction "Затвор(Gate)_1") (pintype "passive"))
      (node (ref "Q2") (pin "3") (pinfunction "Сток(Drain)_3") (pintype "passive"))
      (node (ref "R26") (pin "1") (pinfunction "1_1") (pintype "passive"))
      (node (ref "VD25") (pin "1") (pinfunction "1_1") (pintype "passive"))
    )
    (net (code "76") (name "VCC12_IN") (class "Default")
      (node (ref "Q1") (pin "3") (pinfunction "Сток(Drain)_3") (pintype "passive"))
      (node (ref "R26") (pin "2") (pinfunction "2_2") (pintype "passive"))
      (node (ref "R27") (pin "2") (pinfunction "2_2") (pintype "passive"))
      (node (ref "T1") (pin "2") (pinfunction "2_2") (pintype "passive"))
      (node (ref "X6") (pin "2") (pinfunction "2_2") (pintype "passive"))
    )
    (net (code "77") (name "unconnected-(J7-Pad1)") (class "Default")
      (node (ref "J7") (pin "1") (pinfunction "1_1") (pintype "passive"))
    )
    (net (code "78") (name "unconnected-(J7-Pad2)") (class "Default")
      (node (ref "J7") (pin "2") (pinfunction "2_2") (pintype "passive"))
    )
    (net (code "79") (name "unconnected-(J7-Pad3)") (class "Default")
      (node (ref "J7") (pin "3") (pinfunction "3_3") (pintype "power_in"))
    )
    (net (code "80") (name "unconnected-(J7-Pad4)") (class "Default")
      (node (ref "J7") (pin "4") (pinfunction "4_4") (pintype "power_in"))
    )
    (net (code "81") (name "unconnected-(J7-Pad5)") (class "Default")
      (node (ref "J7") (pin "5") (pinfunction "5_5") (pintype "power_in"))
    )
    (net (code "82") (name "unconnected-(J7-Pad6)") (class "Default")
      (node (ref "J7") (pin "6") (pinfunction "6_6") (pintype "power_in"))
    )
    (net (code "83") (name "unconnected-(J7-Pad7)") (class "Default")
      (node (ref "J7") (pin "7") (pinfunction "7_7") (pintype "power_in"))
    )
    (net (code "84") (name "unconnected-(J7-Pad8)") (class "Default")
      (node (ref "J7") (pin "8") (pinfunction "8_8") (pintype "power_in"))
    )
    (net (code "85") (name "unconnected-(J7-Pad9)") (class "Default")
      (node (ref "J7") (pin "9") (pinfunction "9_9") (pintype "power_in"))
    )
    (net (code "86") (name "unconnected-(J7-Pad10)") (class "Default")
      (node (ref "J7") (pin "10") (pinfunction "10_10") (pintype "power_in"))
    )
    (net (code "87") (name "unconnected-(J7-Pad11)") (class "Default")
      (node (ref "J7") (pin "11") (pinfunction "11_11") (pintype "power_in"))
    )
    (net (code "88") (name "unconnected-(J7-Pad12)") (class "Default")
      (node (ref "J7") (pin "12") (pinfunction "12_12") (pintype "power_in"))
    )
    (net (code "89") (name "unconnected-(J7-Pad13)") (class "Default")
      (node (ref "J7") (pin "13") (pinfunction "13_13") (pintype "power_in"))
    )
    (net (code "90") (name "unconnected-(J7-Pad14)") (class "Default")
      (node (ref "J7") (pin "14") (pinfunction "14_14") (pintype "power_in"))
    )
    (net (code "91") (name "unconnected-(J7-Pad15)") (class "Default")
      (node (ref "J7") (pin "15") (pinfunction "15_15") (pintype "power_in"))
    )
    (net (code "92") (name "unconnected-(J7-Pad16)") (class "Default")
      (node (ref "J7") (pin "16") (pinfunction "16_16") (pintype "power_in"))
    )
    (net (code "93") (name "unconnected-(J7-Pad17)") (class "Default")
      (node (ref "J7") (pin "17") (pinfunction "17_17") (pintype "power_in"))
    )
    (net (code "94") (name "unconnected-(J7-Pad18)") (class "Default")
      (node (ref "J7") (pin "18") (pinfunction "18_18") (pintype "power_in"))
    )
    (net (code "95") (name "unconnected-(J7-Pad19)") (class "Default")
      (node (ref "J7") (pin "19") (pinfunction "19_19") (pintype "power_in"))
    )
    (net (code "96") (name "unconnected-(J7-Pad20)") (class "Default")
      (node (ref "J7") (pin "20") (pinfunction "20_20") (pintype "power_in"))
    )
    (net (code "97") (name "unconnected-(J7-Pad21)") (class "Default")
      (node (ref "J7") (pin "21") (pinfunction "21_21") (pintype "power_in"))
    )
    (net (code "98") (name "unconnected-(MicroSD-DAT1-Pad8)") (class "Default")
      (node (ref "MicroSD") (pin "8") (pinfunction "DAT1_8") (pintype "passive+no_connect"))
    )
    (net (code "99") (name "unconnected-(MicroSD-DAT2-Pad1)") (class "Default")
      (node (ref "MicroSD") (pin "1") (pinfunction "DAT2_1") (pintype "passive+no_connect"))
    )
    (net (code "100") (name "unconnected-(X1-GPIO0-Pad3)") (class "Default")
      (node (ref "X1") (pin "3") (pinfunction "GPIO0_3") (pintype "passive+no_connect"))
    )
    (net (code "101") (name "unconnected-(X1-GPIO2-Pad2)") (class "Default")
      (node (ref "X1") (pin "2") (pinfunction "GPIO2_2") (pintype "passive+no_connect"))
    )
    (net (code "102") (name "unconnected-(X1-GPIO16-Pad7)") (class "Default")
      (node (ref "X1") (pin "7") (pinfunction "GPIO16_7") (pintype "passive+no_connect"))
    )
    (net (code "103") (name "unconnected-(X2-NC-Pad23)") (class "Default")
      (node (ref "X2") (pin "23") (pinfunction "NC_23") (pintype "passive+no_connect"))
    )
    (net (code "104") (name "unconnected-(X2-NC-Pad24)") (class "Default")
      (node (ref "X2") (pin "24") (pinfunction "NC_24") (pintype "passive+no_connect"))
    )
    (net (code "105") (name "unconnected-(X2-NC-Pad25)") (class "Default")
      (node (ref "X2") (pin "25") (pinfunction "NC_25") (pintype "passive+no_connect"))
    )
    (net (code "106") (name "unconnected-(X2-NC-Pad27)") (class "Default")
      (node (ref "X2") (pin "27") (pinfunction "NC_27") (pintype "passive+no_connect"))
    )
    (net (code "107") (name "unconnected-(X2-NC-Pad28)") (class "Default")
      (node (ref "X2") (pin "28") (pinfunction "NC_28") (pintype "passive+no_connect"))
    )
    (net (code "108") (name "unconnected-(X2-NC-Pad29)") (class "Default")
      (node (ref "X2") (pin "29") (pinfunction "NC_29") (pintype "passive+no_connect"))
    )
    (net (code "109") (name "unconnected-(X2-NC-Pad30)") (class "Default")
      (node (ref "X2") (pin "30") (pinfunction "NC_30") (pintype "passive+no_connect"))
    )
    (net (code "110") (name "unconnected-(X2-RESET-Pad37)") (class "Default")
      (node (ref "X2") (pin "37") (pinfunction "RESET_37") (pintype "passive+no_connect"))
    )
    (net (code "111") (name "unconnected-(X2-SD_CLK-Pad33)") (class "Default")
      (node (ref "X2") (pin "33") (pinfunction "SD_CLK_33") (pintype "passive+no_connect"))
    )
    (net (code "112") (name "unconnected-(X2-SD_CS-Pad34)") (class "Default")
      (node (ref "X2") (pin "34") (pinfunction "SD_CS_34") (pintype "passive+no_connect"))
    )
    (net (code "113") (name "unconnected-(X2-SD_MISO-Pad31)") (class "Default")
      (node (ref "X2") (pin "31") (pinfunction "SD_MISO_31") (pintype "passive+no_connect"))
    )
    (net (code "114") (name "unconnected-(X2-SD_MOSI-Pad32)") (class "Default")
      (node (ref "X2") (pin "32") (pinfunction "SD_MOSI_32") (pintype "passive+no_connect"))
    )
  )
)
